# helmholtz_cage_pcb_design.net
KiCad netlist of a schematic drawn in EAGLE
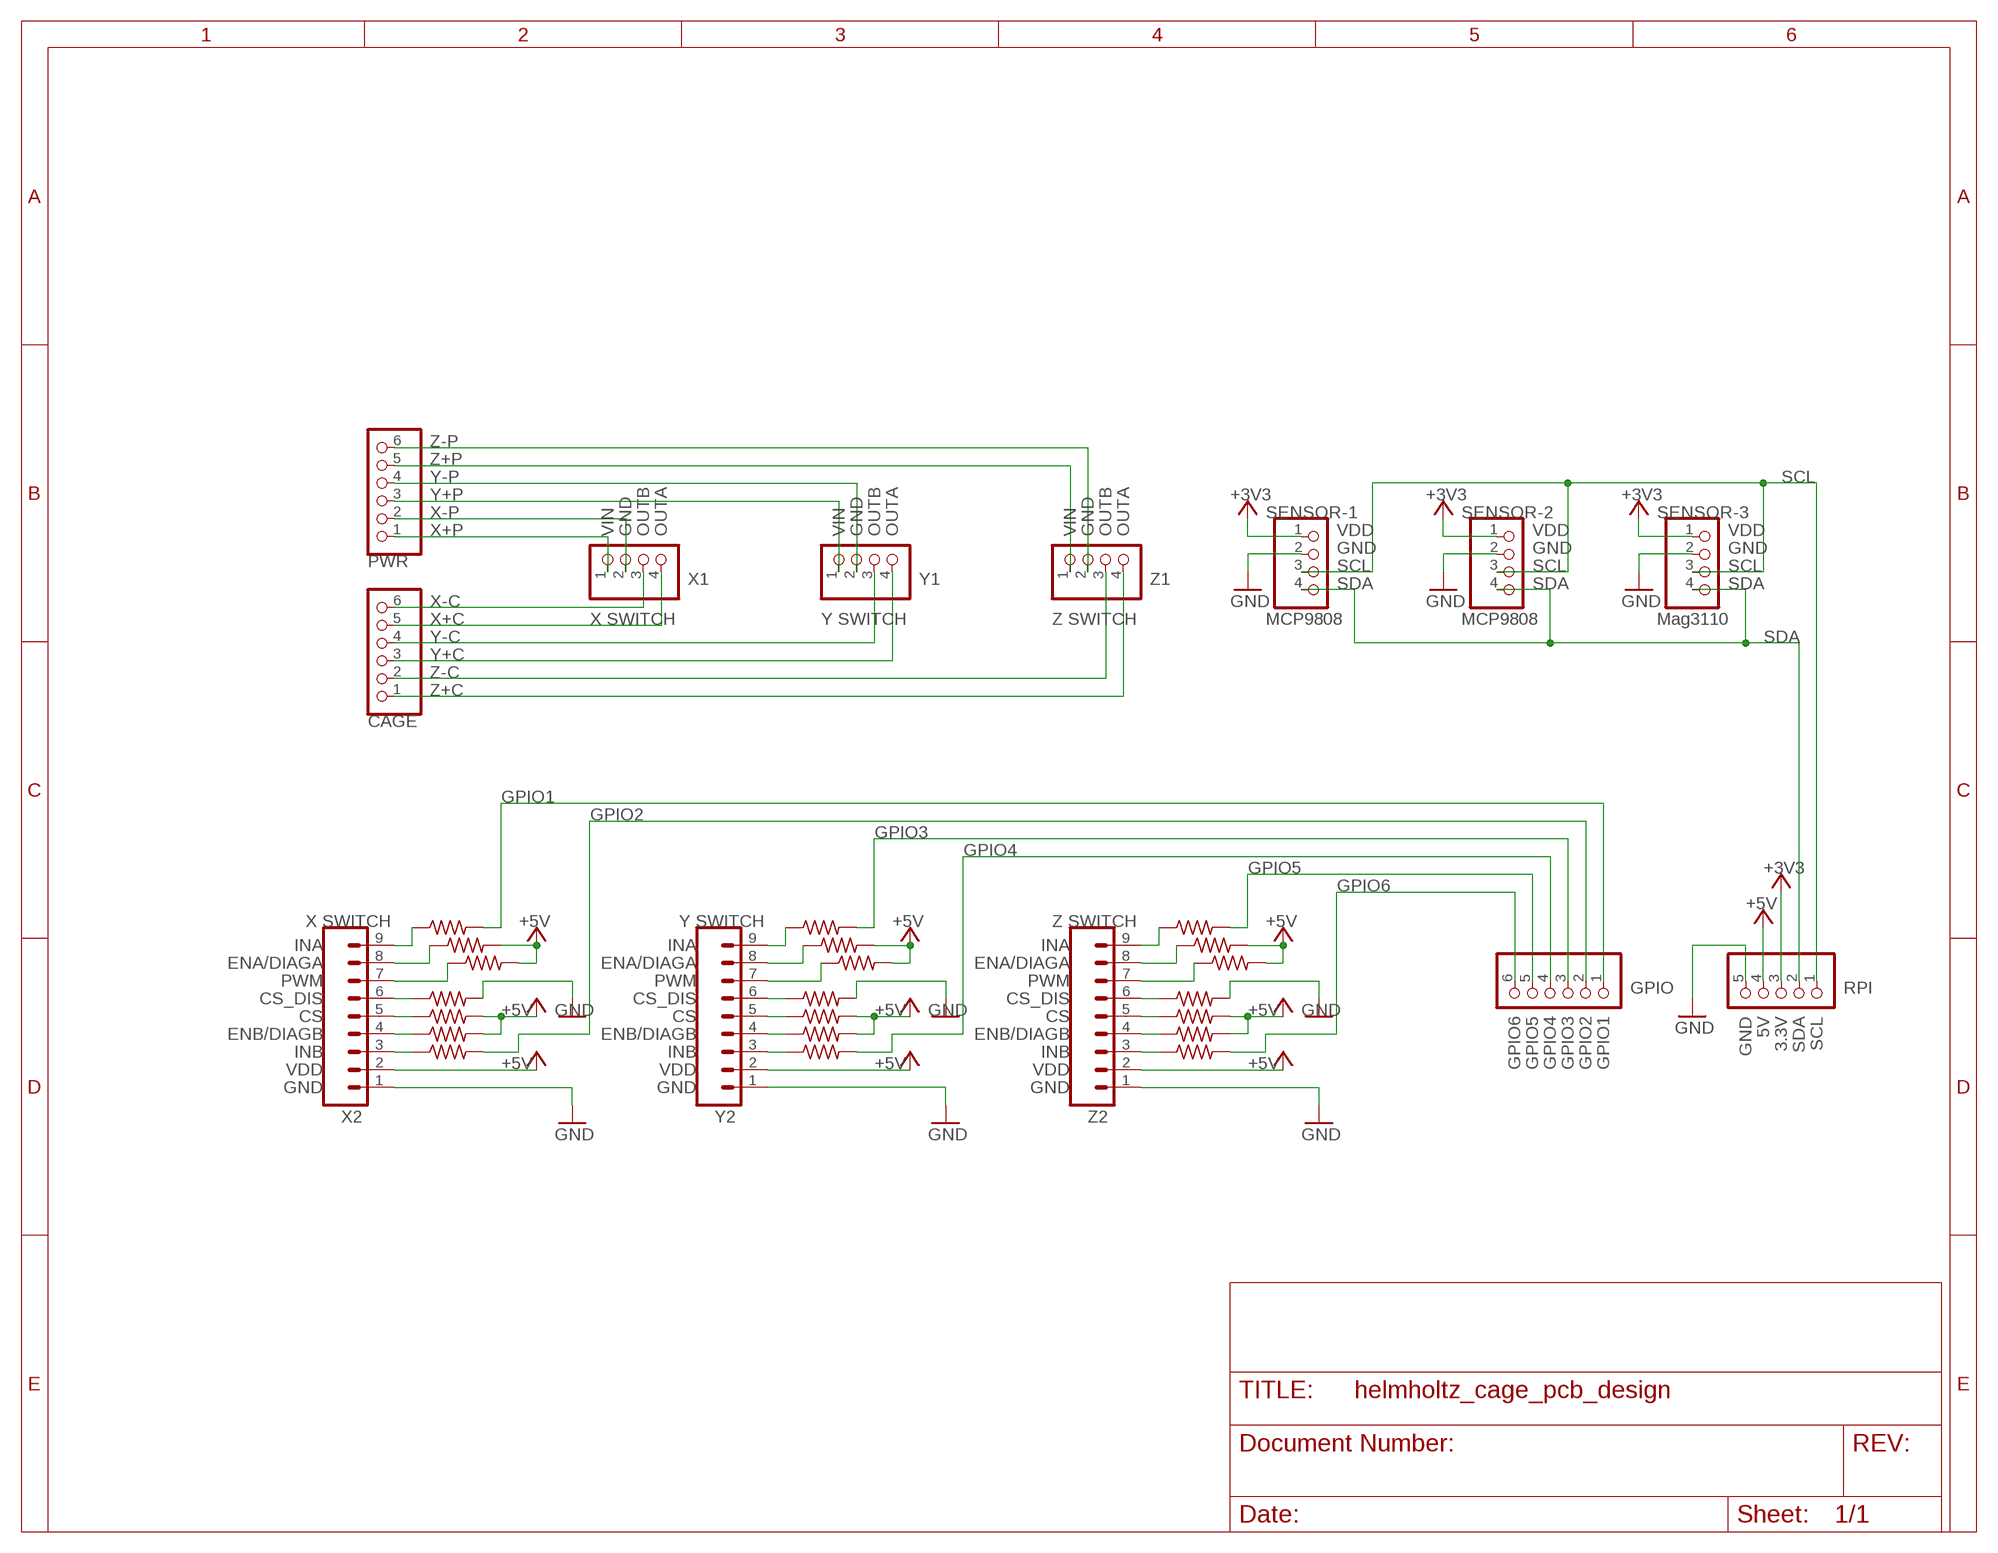
[diagram p0: schematic, sheet 1]

(export (version "E")
  (design (tool "Eeschema 10.0.6"))
  (components
    (comp (ref "CAGE")
      (value "PINHD-1X6")
      (footprint "eagle-import:1X06")
      (libsource (lib "eagle-import") (part "PINHD-1X6"))
    )
    (comp (ref "GPIO")
      (value "PINHD-1X6")
      (footprint "eagle-import:1X06")
      (libsource (lib "eagle-import") (part "PINHD-1X6"))
    )
    (comp (ref "PWR")
      (value "PINHD-1X6")
      (footprint "eagle-import:1X06")
      (libsource (lib "eagle-import") (part "PINHD-1X6"))
    )
    (comp (ref "R1")
      (value "R-US_0204/7")
      (footprint "eagle-import:0204_7")
      (libsource (lib "eagle-import") (part "R-US_0204/7"))
    )
    (comp (ref "R2")
      (value "R-US_0204/7")
      (footprint "eagle-import:0204_7")
      (libsource (lib "eagle-import") (part "R-US_0204/7"))
    )
    (comp (ref "R3")
      (value "R-US_0204/7")
      (footprint "eagle-import:0204_7")
      (libsource (lib "eagle-import") (part "R-US_0204/7"))
    )
    (comp (ref "R4")
      (value "R-US_0204/7")
      (footprint "eagle-import:0204_7")
      (libsource (lib "eagle-import") (part "R-US_0204/7"))
    )
    (comp (ref "R5")
      (value "R-US_0204/7")
      (footprint "eagle-import:0204_7")
      (libsource (lib "eagle-import") (part "R-US_0204/7"))
    )
    (comp (ref "R6")
      (value "R-US_0204/7")
      (footprint "eagle-import:0204_7")
      (libsource (lib "eagle-import") (part "R-US_0204/7"))
    )
    (comp (ref "R7")
      (value "R-US_0204/7")
      (footprint "eagle-import:0204_7")
      (libsource (lib "eagle-import") (part "R-US_0204/7"))
    )
    (comp (ref "R8")
      (value "R-US_0204/7")
      (footprint "eagle-import:0204_7")
      (libsource (lib "eagle-import") (part "R-US_0204/7"))
    )
    (comp (ref "R9")
      (value "R-US_0204/7")
      (footprint "eagle-import:0204_7")
      (libsource (lib "eagle-import") (part "R-US_0204/7"))
    )
    (comp (ref "R10")
      (value "R-US_0204/7")
      (footprint "eagle-import:0204_7")
      (libsource (lib "eagle-import") (part "R-US_0204/7"))
    )
    (comp (ref "R11")
      (value "R-US_0204/7")
      (footprint "eagle-import:0204_7")
      (libsource (lib "eagle-import") (part "R-US_0204/7"))
    )
    (comp (ref "R12")
      (value "R-US_0204/7")
      (footprint "eagle-import:0204_7")
      (libsource (lib "eagle-import") (part "R-US_0204/7"))
    )
    (comp (ref "R13")
      (value "R-US_0204/7")
      (footprint "eagle-import:0204_7")
      (libsource (lib "eagle-import") (part "R-US_0204/7"))
    )
    (comp (ref "R14")
      (value "R-US_0204/7")
      (footprint "eagle-import:0204_7")
      (libsource (lib "eagle-import") (part "R-US_0204/7"))
    )
    (comp (ref "R15")
      (value "R-US_0204/7")
      (footprint "eagle-import:0204_7")
      (libsource (lib "eagle-import") (part "R-US_0204/7"))
    )
    (comp (ref "R16")
      (value "R-US_0204/7")
      (footprint "eagle-import:0204_7")
      (libsource (lib "eagle-import") (part "R-US_0204/7"))
    )
    (comp (ref "R17")
      (value "R-US_0204/7")
      (footprint "eagle-import:0204_7")
      (libsource (lib "eagle-import") (part "R-US_0204/7"))
    )
    (comp (ref "R18")
      (value "R-US_0204/7")
      (footprint "eagle-import:0204_7")
      (libsource (lib "eagle-import") (part "R-US_0204/7"))
    )
    (comp (ref "R19")
      (value "R-US_0204/7")
      (footprint "eagle-import:0204_7")
      (libsource (lib "eagle-import") (part "R-US_0204/7"))
    )
    (comp (ref "R20")
      (value "R-US_0204/7")
      (footprint "eagle-import:0204_7")
      (libsource (lib "eagle-import") (part "R-US_0204/7"))
    )
    (comp (ref "R21")
      (value "R-US_0204/7")
      (footprint "eagle-import:0204_7")
      (libsource (lib "eagle-import") (part "R-US_0204/7"))
    )
    (comp (ref "RPI")
      (value "PINHD-1X5")
      (footprint "eagle-import:1X05")
      (libsource (lib "eagle-import") (part "PINHD-1X5"))
    )
    (comp (ref "SENSOR-1")
      (value "PINHD-1X4")
      (footprint "eagle-import:1X04")
      (libsource (lib "eagle-import") (part "PINHD-1X4"))
    )
    (comp (ref "SENSOR-2")
      (value "PINHD-1X4")
      (footprint "eagle-import:1X04")
      (libsource (lib "eagle-import") (part "PINHD-1X4"))
    )
    (comp (ref "SENSOR-3")
      (value "PINHD-1X4")
      (footprint "eagle-import:1X04")
      (libsource (lib "eagle-import") (part "PINHD-1X4"))
    )
    (comp (ref "X1")
      (value "PINHD-1X4")
      (footprint "eagle-import:1X04")
      (libsource (lib "eagle-import") (part "PINHD-1X4"))
    )
    (comp (ref "X2")
      (value "CONN_09")
      (footprint "eagle-import:1X09")
      (libsource (lib "eagle-import") (part "CONN_09"))
    )
    (comp (ref "Y1")
      (value "PINHD-1X4")
      (footprint "eagle-import:1X04")
      (libsource (lib "eagle-import") (part "PINHD-1X4"))
    )
    (comp (ref "Y2")
      (value "CONN_09")
      (footprint "eagle-import:1X09")
      (libsource (lib "eagle-import") (part "CONN_09"))
    )
    (comp (ref "Z1")
      (value "PINHD-1X4")
      (footprint "eagle-import:1X04")
      (libsource (lib "eagle-import") (part "PINHD-1X4"))
    )
    (comp (ref "Z2")
      (value "CONN_09")
      (footprint "eagle-import:1X09")
      (libsource (lib "eagle-import") (part "CONN_09"))
    )
  )
  (nets
    (net (code "1") (name "+3V3") (class "Default")
      (node (ref "RPI") (pin "3") (pinfunction "3_3") (pintype "passive"))
      (node (ref "SENSOR-1") (pin "1") (pinfunction "1_1") (pintype "passive"))
      (node (ref "SENSOR-2") (pin "1") (pinfunction "1_1") (pintype "passive"))
      (node (ref "SENSOR-3") (pin "1") (pinfunction "1_1") (pintype "passive"))
    )
    (net (code "2") (name "+5V") (class "Default")
      (node (ref "R10") (pin "2") (pinfunction "2_2") (pintype "passive"))
      (node (ref "R11") (pin "2") (pinfunction "2_2") (pintype "passive"))
      (node (ref "R12") (pin "2") (pinfunction "2_2") (pintype "passive"))
      (node (ref "R17") (pin "2") (pinfunction "2_2") (pintype "passive"))
      (node (ref "R18") (pin "2") (pinfunction "2_2") (pintype "passive"))
      (node (ref "R19") (pin "2") (pinfunction "2_2") (pintype "passive"))
      (node (ref "R21") (pin "2") (pinfunction "2_2") (pintype "passive"))
      (node (ref "R3") (pin "2") (pinfunction "2_2") (pintype "passive"))
      (node (ref "R4") (pin "2") (pinfunction "2_2") (pintype "passive"))
      (node (ref "R5") (pin "2") (pinfunction "2_2") (pintype "passive"))
      (node (ref "R7") (pin "2") (pinfunction "2_2") (pintype "passive"))
      (node (ref "R8") (pin "2") (pinfunction "2_2") (pintype "passive"))
      (node (ref "RPI") (pin "4") (pinfunction "4_4") (pintype "passive"))
      (node (ref "X2") (pin "2") (pinfunction "2_2") (pintype "passive"))
      (node (ref "Y2") (pin "2") (pinfunction "2_2") (pintype "passive"))
      (node (ref "Z2") (pin "2") (pinfunction "2_2") (pintype "passive"))
    )
    (net (code "3") (name "/GPIO1") (class "Default")
      (node (ref "GPIO") (pin "1") (pinfunction "1_1") (pintype "passive"))
      (node (ref "R1") (pin "2") (pinfunction "2_2") (pintype "passive"))
    )
    (net (code "4") (name "/GPIO2") (class "Default")
      (node (ref "GPIO") (pin "2") (pinfunction "2_2") (pintype "passive"))
      (node (ref "R2") (pin "2") (pinfunction "2_2") (pintype "passive"))
    )
    (net (code "5") (name "/GPIO3") (class "Default")
      (node (ref "GPIO") (pin "3") (pinfunction "3_3") (pintype "passive"))
      (node (ref "R14") (pin "2") (pinfunction "2_2") (pintype "passive"))
    )
    (net (code "6") (name "/GPIO4") (class "Default")
      (node (ref "GPIO") (pin "4") (pinfunction "4_4") (pintype "passive"))
      (node (ref "R13") (pin "2") (pinfunction "2_2") (pintype "passive"))
    )
    (net (code "7") (name "/GPIO5") (class "Default")
      (node (ref "GPIO") (pin "5") (pinfunction "5_5") (pintype "passive"))
      (node (ref "R15") (pin "2") (pinfunction "2_2") (pintype "passive"))
    )
    (net (code "8") (name "/GPIO6") (class "Default")
      (node (ref "GPIO") (pin "6") (pinfunction "6_6") (pintype "passive"))
      (node (ref "R16") (pin "2") (pinfunction "2_2") (pintype "passive"))
    )
    (net (code "9") (name "/X+C") (class "Default")
      (node (ref "CAGE") (pin "5") (pinfunction "5_5") (pintype "passive"))
      (node (ref "X1") (pin "4") (pinfunction "4_4") (pintype "passive"))
    )
    (net (code "10") (name "/X+P") (class "Default")
      (node (ref "PWR") (pin "1") (pinfunction "1_1") (pintype "passive"))
      (node (ref "X1") (pin "1") (pinfunction "1_1") (pintype "passive"))
    )
    (net (code "11") (name "/X-C") (class "Default")
      (node (ref "CAGE") (pin "6") (pinfunction "6_6") (pintype "passive"))
      (node (ref "X1") (pin "3") (pinfunction "3_3") (pintype "passive"))
    )
    (net (code "12") (name "/X-P") (class "Default")
      (node (ref "PWR") (pin "2") (pinfunction "2_2") (pintype "passive"))
      (node (ref "X1") (pin "2") (pinfunction "2_2") (pintype "passive"))
    )
    (net (code "13") (name "/Y+C") (class "Default")
      (node (ref "CAGE") (pin "3") (pinfunction "3_3") (pintype "passive"))
      (node (ref "Y1") (pin "4") (pinfunction "4_4") (pintype "passive"))
    )
    (net (code "14") (name "/Y+P") (class "Default")
      (node (ref "PWR") (pin "3") (pinfunction "3_3") (pintype "passive"))
      (node (ref "Y1") (pin "1") (pinfunction "1_1") (pintype "passive"))
    )
    (net (code "15") (name "/Y-C") (class "Default")
      (node (ref "CAGE") (pin "4") (pinfunction "4_4") (pintype "passive"))
      (node (ref "Y1") (pin "3") (pinfunction "3_3") (pintype "passive"))
    )
    (net (code "16") (name "/Y-P") (class "Default")
      (node (ref "PWR") (pin "4") (pinfunction "4_4") (pintype "passive"))
      (node (ref "Y1") (pin "2") (pinfunction "2_2") (pintype "passive"))
    )
    (net (code "17") (name "/Z+C") (class "Default")
      (node (ref "CAGE") (pin "1") (pinfunction "1_1") (pintype "passive"))
      (node (ref "Z1") (pin "4") (pinfunction "4_4") (pintype "passive"))
    )
    (net (code "18") (name "/Z+P") (class "Default")
      (node (ref "PWR") (pin "5") (pinfunction "5_5") (pintype "passive"))
      (node (ref "Z1") (pin "1") (pinfunction "1_1") (pintype "passive"))
    )
    (net (code "19") (name "/Z-C") (class "Default")
      (node (ref "CAGE") (pin "2") (pinfunction "2_2") (pintype "passive"))
      (node (ref "Z1") (pin "3") (pinfunction "3_3") (pintype "passive"))
    )
    (net (code "20") (name "/Z-P") (class "Default")
      (node (ref "PWR") (pin "6") (pinfunction "6_6") (pintype "passive"))
      (node (ref "Z1") (pin "2") (pinfunction "2_2") (pintype "passive"))
    )
    (net (code "21") (name "GND") (class "Default")
      (node (ref "R20") (pin "2") (pinfunction "2_2") (pintype "passive"))
      (node (ref "R6") (pin "2") (pinfunction "2_2") (pintype "passive"))
      (node (ref "R9") (pin "2") (pinfunction "2_2") (pintype "passive"))
      (node (ref "RPI") (pin "5") (pinfunction "5_5") (pintype "passive"))
      (node (ref "SENSOR-1") (pin "2") (pinfunction "2_2") (pintype "passive"))
      (node (ref "SENSOR-2") (pin "2") (pinfunction "2_2") (pintype "passive"))
      (node (ref "SENSOR-3") (pin "2") (pinfunction "2_2") (pintype "passive"))
      (node (ref "X2") (pin "1") (pinfunction "1_1") (pintype "passive"))
      (node (ref "Y2") (pin "1") (pinfunction "1_1") (pintype "passive"))
      (node (ref "Z2") (pin "1") (pinfunction "1_1") (pintype "passive"))
    )
    (net (code "22") (name "Net-(R1-Pad1)") (class "Default")
      (node (ref "R1") (pin "1") (pinfunction "1_1") (pintype "passive"))
      (node (ref "X2") (pin "9") (pinfunction "9_9") (pintype "passive"))
    )
    (net (code "23") (name "Net-(R2-Pad1)") (class "Default")
      (node (ref "R2") (pin "1") (pinfunction "1_1") (pintype "passive"))
      (node (ref "X2") (pin "3") (pinfunction "3_3") (pintype "passive"))
    )
    (net (code "24") (name "Net-(R3-Pad1)") (class "Default")
      (node (ref "R3") (pin "1") (pinfunction "1_1") (pintype "passive"))
      (node (ref "X2") (pin "8") (pinfunction "8_8") (pintype "passive"))
    )
    (net (code "25") (name "Net-(R4-Pad1)") (class "Default")
      (node (ref "R4") (pin "1") (pinfunction "1_1") (pintype "passive"))
      (node (ref "X2") (pin "4") (pinfunction "4_4") (pintype "passive"))
    )
    (net (code "26") (name "Net-(R5-Pad1)") (class "Default")
      (node (ref "R5") (pin "1") (pinfunction "1_1") (pintype "passive"))
      (node (ref "X2") (pin "7") (pinfunction "7_7") (pintype "passive"))
    )
    (net (code "27") (name "Net-(R6-Pad1)") (class "Default")
      (node (ref "R6") (pin "1") (pinfunction "1_1") (pintype "passive"))
      (node (ref "X2") (pin "6") (pinfunction "6_6") (pintype "passive"))
    )
    (net (code "28") (name "Net-(R7-Pad1)") (class "Default")
      (node (ref "R7") (pin "1") (pinfunction "1_1") (pintype "passive"))
      (node (ref "X2") (pin "5") (pinfunction "5_5") (pintype "passive"))
    )
    (net (code "29") (name "Net-(R8-Pad1)") (class "Default")
      (node (ref "R8") (pin "1") (pinfunction "1_1") (pintype "passive"))
      (node (ref "Y2") (pin "5") (pinfunction "5_5") (pintype "passive"))
    )
    (net (code "30") (name "Net-(R9-Pad1)") (class "Default")
      (node (ref "R9") (pin "1") (pinfunction "1_1") (pintype "passive"))
      (node (ref "Y2") (pin "6") (pinfunction "6_6") (pintype "passive"))
    )
    (net (code "31") (name "Net-(R10-Pad1)") (class "Default")
      (node (ref "R10") (pin "1") (pinfunction "1_1") (pintype "passive"))
      (node (ref "Y2") (pin "7") (pinfunction "7_7") (pintype "passive"))
    )
    (net (code "32") (name "Net-(R11-Pad1)") (class "Default")
      (node (ref "R11") (pin "1") (pinfunction "1_1") (pintype "passive"))
      (node (ref "Y2") (pin "4") (pinfunction "4_4") (pintype "passive"))
    )
    (net (code "33") (name "Net-(R12-Pad1)") (class "Default")
      (node (ref "R12") (pin "1") (pinfunction "1_1") (pintype "passive"))
      (node (ref "Y2") (pin "8") (pinfunction "8_8") (pintype "passive"))
    )
    (net (code "34") (name "Net-(R13-Pad1)") (class "Default")
      (node (ref "R13") (pin "1") (pinfunction "1_1") (pintype "passive"))
      (node (ref "Y2") (pin "3") (pinfunction "3_3") (pintype "passive"))
    )
    (net (code "35") (name "Net-(R14-Pad1)") (class "Default")
      (node (ref "R14") (pin "1") (pinfunction "1_1") (pintype "passive"))
      (node (ref "Y2") (pin "9") (pinfunction "9_9") (pintype "passive"))
    )
    (net (code "36") (name "Net-(R15-Pad1)") (class "Default")
      (node (ref "R15") (pin "1") (pinfunction "1_1") (pintype "passive"))
      (node (ref "Z2") (pin "9") (pinfunction "9_9") (pintype "passive"))
    )
    (net (code "37") (name "Net-(R16-Pad1)") (class "Default")
      (node (ref "R16") (pin "1") (pinfunction "1_1") (pintype "passive"))
      (node (ref "Z2") (pin "3") (pinfunction "3_3") (pintype "passive"))
    )
    (net (code "38") (name "Net-(R17-Pad1)") (class "Default")
      (node (ref "R17") (pin "1") (pinfunction "1_1") (pintype "passive"))
      (node (ref "Z2") (pin "8") (pinfunction "8_8") (pintype "passive"))
    )
    (net (code "39") (name "Net-(R18-Pad1)") (class "Default")
      (node (ref "R18") (pin "1") (pinfunction "1_1") (pintype "passive"))
      (node (ref "Z2") (pin "4") (pinfunction "4_4") (pintype "passive"))
    )
    (net (code "40") (name "Net-(R19-Pad1)") (class "Default")
      (node (ref "R19") (pin "1") (pinfunction "1_1") (pintype "passive"))
      (node (ref "Z2") (pin "7") (pinfunction "7_7") (pintype "passive"))
    )
    (net (code "41") (name "Net-(R20-Pad1)") (class "Default")
      (node (ref "R20") (pin "1") (pinfunction "1_1") (pintype "passive"))
      (node (ref "Z2") (pin "6") (pinfunction "6_6") (pintype "passive"))
    )
    (net (code "42") (name "Net-(R21-Pad1)") (class "Default")
      (node (ref "R21") (pin "1") (pinfunction "1_1") (pintype "passive"))
      (node (ref "Z2") (pin "5") (pinfunction "5_5") (pintype "passive"))
    )
    (net (code "43") (name "Net-(RPI-Pad1)") (class "Default")
      (node (ref "RPI") (pin "1") (pinfunction "1_1") (pintype "passive"))
      (node (ref "SENSOR-1") (pin "3") (pinfunction "3_3") (pintype "passive"))
      (node (ref "SENSOR-2") (pin "3") (pinfunction "3_3") (pintype "passive"))
      (node (ref "SENSOR-3") (pin "3") (pinfunction "3_3") (pintype "passive"))
    )
    (net (code "44") (name "Net-(RPI-Pad2)") (class "Default")
      (node (ref "RPI") (pin "2") (pinfunction "2_2") (pintype "passive"))
      (node (ref "SENSOR-1") (pin "4") (pinfunction "4_4") (pintype "passive"))
      (node (ref "SENSOR-2") (pin "4") (pinfunction "4_4") (pintype "passive"))
      (node (ref "SENSOR-3") (pin "4") (pinfunction "4_4") (pintype "passive"))
    )
  )
)
